# RCNetwork.net
KiCad netlist of a schematic drawn in Altium Designer
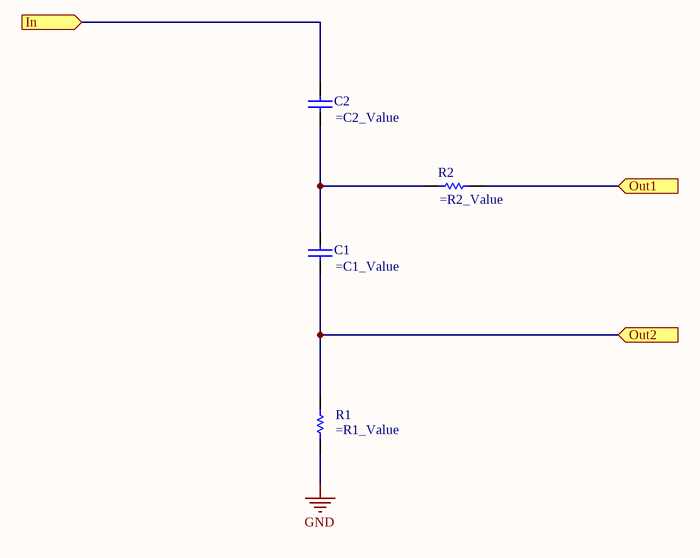
[diagram p0: RCNetwork.SchDoc]

(export (version "E")
  (design (tool "Eeschema 10.0.6"))
  (components
    (comp (ref "C1")
      (value "~")
      (footprint "AudioEqualizer:C1206")
      (description "Capacitor")
      (fields (field (name "PUBLISHER") "Altium Limited"))
      (libsource (lib "Miscellaneous Devices") (part "Cap"))
    )
    (comp (ref "C2")
      (value "~")
      (footprint "AudioEqualizer:C1206")
      (description "Capacitor")
      (fields (field (name "PUBLISHER") "Altium Limited"))
      (libsource (lib "Miscellaneous Devices") (part "Cap"))
    )
    (comp (ref "R1")
      (value "~")
      (footprint "AudioEqualizer:3216[1206]")
      (description "Resistor")
      (fields (field (name "PUBLISHER") "Altium Limited"))
      (libsource (lib "Miscellaneous Devices") (part "Res1"))
    )
    (comp (ref "R2")
      (value "~")
      (footprint "AudioEqualizer:3216[1206]")
      (description "Resistor")
      (fields (field (name "PUBLISHER") "Altium Limited"))
      (libsource (lib "Miscellaneous Devices") (part "Res1"))
    )
  )
  (nets
    (net (code "1") (name "/In") (class "Default")
      (node (ref "C2") (pin "1") (pinfunction "1_1") (pintype "passive"))
    )
    (net (code "2") (name "/Out1") (class "Default")
      (node (ref "R2") (pin "1") (pinfunction "1_1") (pintype "passive"))
    )
    (net (code "3") (name "/Out2") (class "Default")
      (node (ref "C1") (pin "2") (pinfunction "2_2") (pintype "passive"))
      (node (ref "R1") (pin "2") (pinfunction "2_2") (pintype "passive"))
    )
    (net (code "4") (name "GND") (class "Default")
      (node (ref "R1") (pin "1") (pinfunction "1_1") (pintype "passive"))
    )
    (net (code "5") (name "Net-(C1-Pad1)") (class "Default")
      (node (ref "C1") (pin "1") (pinfunction "1_1") (pintype "passive"))
      (node (ref "C2") (pin "2") (pinfunction "2_2") (pintype "passive"))
      (node (ref "R2") (pin "2") (pinfunction "2_2") (pintype "passive"))
    )
  )
)
